# IO.net
KiCad netlist of a schematic drawn in Altium Designer
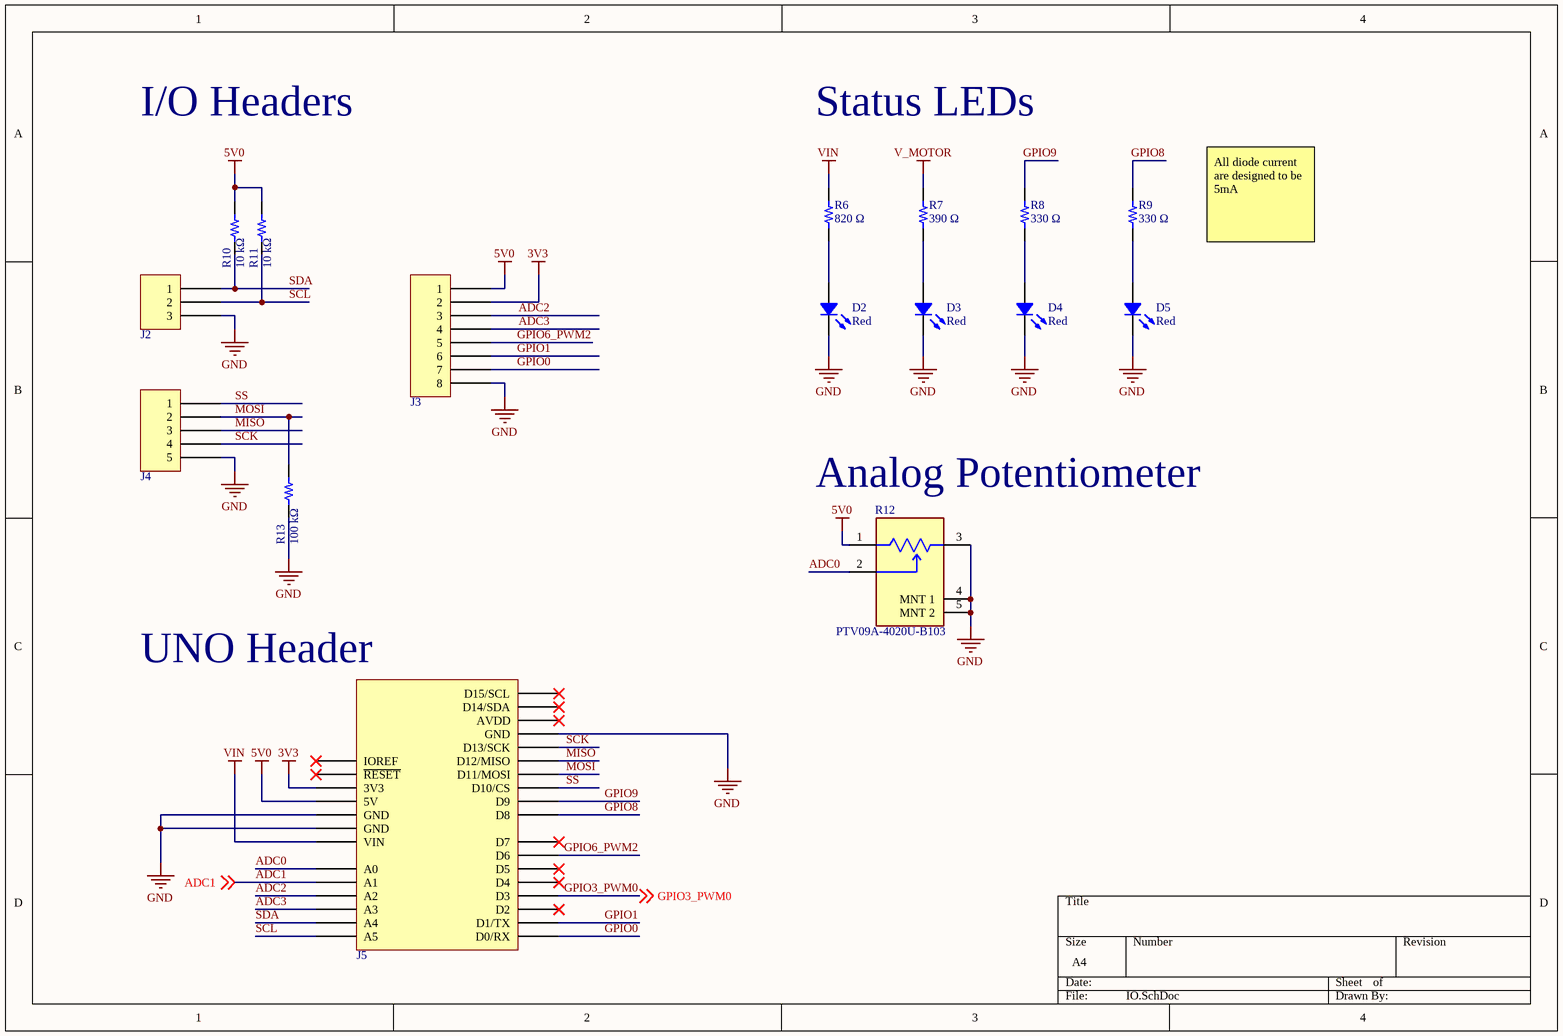
[diagram p0: IO.SchDoc]

(export (version "E")
  (design (tool "Eeschema 10.0.6"))
  (components
    (comp (ref "D2")
      (value "Red")
      (footprint "LED 0603_1608 RED")
      (description "LED RED DIFFUSED 0603 SMD")
      (fields (field (name "PART NUMBER") "150060SS55040") (field (name "MANUFACTURER") "Würth Elektronik"))
      (libsource (lib "Generic Altium Database") (part "LED"))
    )
    (comp (ref "D3")
      (value "Red")
      (footprint "LED 0603_1608 RED")
      (description "LED RED DIFFUSED 0603 SMD")
      (fields (field (name "PART NUMBER") "150060SS55040") (field (name "MANUFACTURER") "Würth Elektronik"))
      (libsource (lib "Generic Altium Database") (part "LED"))
    )
    (comp (ref "D4")
      (value "Red")
      (footprint "LED 0603_1608 RED")
      (description "LED RED DIFFUSED 0603 SMD")
      (fields (field (name "PART NUMBER") "150060SS55040") (field (name "MANUFACTURER") "Würth Elektronik"))
      (libsource (lib "Generic Altium Database") (part "LED"))
    )
    (comp (ref "D5")
      (value "Red")
      (footprint "LED 0603_1608 RED")
      (description "LED RED DIFFUSED 0603 SMD")
      (fields (field (name "PART NUMBER") "150060SS55040") (field (name "MANUFACTURER") "Würth Elektronik"))
      (libsource (lib "Generic Altium Database") (part "LED"))
    )
    (comp (ref "J2")
      (value "0022272031")
      (footprint "MOLEX KK 0022272031")
      (description "CONN HEADER VERT 3POS 2.54MM")
      (fields (field (name "MANUFACTURER") "Molex"))
      (libsource (lib "Generic Altium Database") (part "3 Pin"))
    )
    (comp (ref "J3")
      (value "0022272081")
      (footprint "MOLEX KK 0022272081")
      (description "CONN HEADER VERT 8POS 2.54MM")
      (fields (field (name "MANUFACTURER") "Molex"))
      (libsource (lib "Generic Altium Database") (part "8 Pin"))
    )
    (comp (ref "J4")
      (value "0022272051")
      (footprint "MOLEX KK 0022272051")
      (description "CONN HEADER VERT 5POS 2.54MM")
      (fields (field (name "MANUFACTURER") "Molex"))
      (libsource (lib "Generic Altium Database") (part "5 Pin"))
    )
    (comp (ref "J5")
      (value "920-0088-01")
      (footprint "SCHMARTBOARD - 920-0088-01")
      (description "CONN HDR 8/10P 0.1 GOLD PCB 6PC")
      (fields (field (name "MANUFACTURER") "Schmartboard, Inc."))
      (libsource (lib "Generic Altium Database") (part "Arduino Headers"))
    )
    (comp (ref "R6")
      (value "820 Ω")
      (footprint "RES 0603_1608")
      (description "RES SMD 820 OHM 1% 1/10W 0603")
      (fields (field (name "PART NUMBER") "AC0603FR-07820RL") (field (name "MANUFACTURER") "Yageo"))
      (libsource (lib "Generic Altium Database") (part "Resistor"))
    )
    (comp (ref "R7")
      (value "390 Ω")
      (footprint "RES 0603_1608")
      (description "RES SMD 390 OHM 5% 1/10W 0603")
      (fields (field (name "PART NUMBER") "AC0603JR-07390RL") (field (name "MANUFACTURER") "Yageo"))
      (libsource (lib "Generic Altium Database") (part "Resistor"))
    )
    (comp (ref "R8")
      (value "330 Ω")
      (footprint "RES 0603_1608")
      (description "RES SMD 330 OHM 1% 1/10W 0603")
      (fields (field (name "PART NUMBER") "AC0603FR-07330RL") (field (name "MANUFACTURER") "Yageo"))
      (libsource (lib "Generic Altium Database") (part "Resistor"))
    )
    (comp (ref "R9")
      (value "330 Ω")
      (footprint "RES 0603_1608")
      (description "RES SMD 330 OHM 1% 1/10W 0603")
      (fields (field (name "PART NUMBER") "AC0603FR-07330RL") (field (name "MANUFACTURER") "Yageo"))
      (libsource (lib "Generic Altium Database") (part "Resistor"))
    )
    (comp (ref "R10")
      (value "10 kΩ")
      (footprint "RES 0603_1608")
      (description "RES SMD 10K OHM 1% 1/10W 0603")
      (fields (field (name "PART NUMBER") "AC0603FR-0710KL") (field (name "MANUFACTURER") "Yageo"))
      (libsource (lib "Generic Altium Database") (part "Resistor"))
    )
    (comp (ref "R11")
      (value "10 kΩ")
      (footprint "RES 0603_1608")
      (description "RES SMD 10K OHM 1% 1/10W 0603")
      (fields (field (name "PART NUMBER") "AC0603FR-0710KL") (field (name "MANUFACTURER") "Yageo"))
      (libsource (lib "Generic Altium Database") (part "Resistor"))
    )
    (comp (ref "R12")
      (value "PTV09A-4020U-B103")
      (footprint "FP-PTV09A-4-MFG")
      (description "POT 10K OHM 1/20W CARBON LINEAR")
      (fields (field (name "TOLERANCE") "20%") (field (name "MANUFACTURER") "Bourns Inc."))
      (libsource (lib "Altium Content Vault") (part "3454c451b146ec4d4239c7813666f62"))
    )
    (comp (ref "R13")
      (value "100 kΩ")
      (footprint "RES 0603_1608")
      (description "RES SMD 100K OHM 1% 1/10W 0603")
      (fields (field (name "PART NUMBER") "AC0603FR-07100KL") (field (name "MANUFACTURER") "Yageo"))
      (libsource (lib "Generic Altium Database") (part "Resistor"))
    )
  )
  (nets
    (net (code "1") (name "/ADC0") (class "Default")
      (node (ref "J5") (pin "9") (pinfunction "A0_9") (pintype "passive"))
      (node (ref "R12") (pin "2") (pinfunction "2_2") (pintype "passive"))
    )
    (net (code "2") (name "/ADC2") (class "Default")
      (node (ref "J3") (pin "3") (pinfunction "3_3") (pintype "passive"))
      (node (ref "J5") (pin "11") (pinfunction "A2_11") (pintype "passive"))
    )
    (net (code "3") (name "/ADC3") (class "Default")
      (node (ref "J3") (pin "4") (pinfunction "4_4") (pintype "passive"))
      (node (ref "J5") (pin "12") (pinfunction "A3_12") (pintype "passive"))
    )
    (net (code "4") (name "/GPIO0") (class "Default")
      (node (ref "J3") (pin "7") (pinfunction "7_7") (pintype "passive"))
      (node (ref "J5") (pin "15") (pinfunction "D0/RX_15") (pintype "passive"))
    )
    (net (code "5") (name "/GPIO1") (class "Default")
      (node (ref "J3") (pin "6") (pinfunction "6_6") (pintype "passive"))
      (node (ref "J5") (pin "16") (pinfunction "D1/TX_16") (pintype "passive"))
    )
    (net (code "6") (name "/GPIO6_PWM2") (class "Default")
      (node (ref "J3") (pin "5") (pinfunction "5_5") (pintype "passive"))
      (node (ref "J5") (pin "21") (pinfunction "D6_21") (pintype "passive"))
    )
    (net (code "7") (name "/GPIO8") (class "Default")
      (node (ref "J5") (pin "23") (pinfunction "D8_23") (pintype "passive"))
      (node (ref "R9") (pin "1") (pinfunction "1_1") (pintype "passive"))
    )
    (net (code "8") (name "/GPIO9") (class "Default")
      (node (ref "J5") (pin "24") (pinfunction "D9_24") (pintype "passive"))
      (node (ref "R8") (pin "1") (pinfunction "1_1") (pintype "passive"))
    )
    (net (code "9") (name "/MISO") (class "Default")
      (node (ref "J4") (pin "3") (pinfunction "3_3") (pintype "passive"))
      (node (ref "J5") (pin "27") (pinfunction "D12/MISO_27") (pintype "passive"))
    )
    (net (code "10") (name "/MOSI") (class "Default")
      (node (ref "J4") (pin "2") (pinfunction "2_2") (pintype "passive"))
      (node (ref "J5") (pin "26") (pinfunction "D11/MOSI_26") (pintype "passive"))
      (node (ref "R13") (pin "1") (pinfunction "1_1") (pintype "passive"))
    )
    (net (code "11") (name "/SCK") (class "Default")
      (node (ref "J4") (pin "4") (pinfunction "4_4") (pintype "passive"))
      (node (ref "J5") (pin "28") (pinfunction "D13/SCK_28") (pintype "passive"))
    )
    (net (code "12") (name "/SCL") (class "Default")
      (node (ref "J2") (pin "2") (pinfunction "2_2") (pintype "passive"))
      (node (ref "J5") (pin "14") (pinfunction "A5_14") (pintype "passive"))
      (node (ref "R11") (pin "2") (pinfunction "2_2") (pintype "passive"))
    )
    (net (code "13") (name "/SDA") (class "Default")
      (node (ref "J2") (pin "1") (pinfunction "1_1") (pintype "passive"))
      (node (ref "J5") (pin "13") (pinfunction "A4_13") (pintype "passive"))
      (node (ref "R10") (pin "2") (pinfunction "2_2") (pintype "passive"))
    )
    (net (code "14") (name "/SS") (class "Default")
      (node (ref "J4") (pin "1") (pinfunction "1_1") (pintype "passive"))
      (node (ref "J5") (pin "25") (pinfunction "D10/CS_25") (pintype "passive"))
    )
    (net (code "15") (name "3V3") (class "Default")
      (node (ref "J3") (pin "2") (pinfunction "2_2") (pintype "passive"))
      (node (ref "J5") (pin "4") (pinfunction "3V3_4") (pintype "passive"))
    )
    (net (code "16") (name "5V0") (class "Default")
      (node (ref "J3") (pin "1") (pinfunction "1_1") (pintype "passive"))
      (node (ref "J5") (pin "5") (pinfunction "5V_5") (pintype "passive"))
      (node (ref "R10") (pin "1") (pinfunction "1_1") (pintype "passive"))
      (node (ref "R11") (pin "1") (pinfunction "1_1") (pintype "passive"))
      (node (ref "R12") (pin "1") (pinfunction "1_1") (pintype "passive"))
    )
    (net (code "17") (name "ADC1") (class "Default")
      (node (ref "J5") (pin "10") (pinfunction "A1_10") (pintype "passive"))
    )
    (net (code "18") (name "GND") (class "Default")
      (node (ref "D2") (pin "2") (pinfunction "2_2") (pintype "passive"))
      (node (ref "D3") (pin "2") (pinfunction "2_2") (pintype "passive"))
      (node (ref "D4") (pin "2") (pinfunction "2_2") (pintype "passive"))
      (node (ref "D5") (pin "2") (pinfunction "2_2") (pintype "passive"))
      (node (ref "J2") (pin "3") (pinfunction "3_3") (pintype "passive"))
      (node (ref "J3") (pin "8") (pinfunction "8_8") (pintype "passive"))
      (node (ref "J4") (pin "5") (pinfunction "5_5") (pintype "passive"))
      (node (ref "J5") (pin "29") (pinfunction "GND_29") (pintype "passive"))
      (node (ref "J5") (pin "6") (pinfunction "GND_6") (pintype "passive"))
      (node (ref "J5") (pin "7") (pinfunction "GND_7") (pintype "passive"))
      (node (ref "R12") (pin "3") (pinfunction "3_3") (pintype "passive"))
      (node (ref "R12") (pin "4") (pinfunction "MNT_1_4") (pintype "passive"))
      (node (ref "R12") (pin "5") (pinfunction "MNT_2_5") (pintype "passive"))
      (node (ref "R13") (pin "2") (pinfunction "2_2") (pintype "passive"))
    )
    (net (code "19") (name "GPIO3_PWM0") (class "Default")
      (node (ref "J5") (pin "18") (pinfunction "D3_18") (pintype "passive"))
    )
    (net (code "20") (name "Net-(D2-Pad1)") (class "Default")
      (node (ref "D2") (pin "1") (pinfunction "1_1") (pintype "passive"))
      (node (ref "R6") (pin "2") (pinfunction "2_2") (pintype "passive"))
    )
    (net (code "21") (name "Net-(D3-Pad1)") (class "Default")
      (node (ref "D3") (pin "1") (pinfunction "1_1") (pintype "passive"))
      (node (ref "R7") (pin "2") (pinfunction "2_2") (pintype "passive"))
    )
    (net (code "22") (name "Net-(D4-Pad1)") (class "Default")
      (node (ref "D4") (pin "1") (pinfunction "1_1") (pintype "passive"))
      (node (ref "R8") (pin "2") (pinfunction "2_2") (pintype "passive"))
    )
    (net (code "23") (name "Net-(D5-Pad1)") (class "Default")
      (node (ref "D5") (pin "1") (pinfunction "1_1") (pintype "passive"))
      (node (ref "R9") (pin "2") (pinfunction "2_2") (pintype "passive"))
    )
    (net (code "24") (name "VIN") (class "Default")
      (node (ref "J5") (pin "8") (pinfunction "VIN_8") (pintype "passive"))
      (node (ref "R6") (pin "1") (pinfunction "1_1") (pintype "passive"))
    )
    (net (code "25") (name "V_MOTOR") (class "Default")
      (node (ref "R7") (pin "1") (pinfunction "1_1") (pintype "passive"))
    )
    (net (code "26") (name "unconnected-(J5-AVDD-Pad30)") (class "Default")
      (node (ref "J5") (pin "30") (pinfunction "AVDD_30") (pintype "passive+no_connect"))
    )
    (net (code "27") (name "unconnected-(J5-D2-Pad17)") (class "Default")
      (node (ref "J5") (pin "17") (pinfunction "D2_17") (pintype "passive+no_connect"))
    )
    (net (code "28") (name "unconnected-(J5-D4-Pad19)") (class "Default")
      (node (ref "J5") (pin "19") (pinfunction "D4_19") (pintype "passive+no_connect"))
    )
    (net (code "29") (name "unconnected-(J5-D5-Pad20)") (class "Default")
      (node (ref "J5") (pin "20") (pinfunction "D5_20") (pintype "passive+no_connect"))
    )
    (net (code "30") (name "unconnected-(J5-D7-Pad22)") (class "Default")
      (node (ref "J5") (pin "22") (pinfunction "D7_22") (pintype "passive+no_connect"))
    )
    (net (code "31") (name "unconnected-(J5-D14{slash}SDA-Pad31)") (class "Default")
      (node (ref "J5") (pin "31") (pinfunction "D14/SDA_31") (pintype "passive+no_connect"))
    )
    (net (code "32") (name "unconnected-(J5-D15{slash}SCL-Pad32)") (class "Default")
      (node (ref "J5") (pin "32") (pinfunction "D15/SCL_32") (pintype "passive+no_connect"))
    )
    (net (code "33") (name "unconnected-(J5-IOREF-Pad2)") (class "Default")
      (node (ref "J5") (pin "2") (pinfunction "IOREF_2") (pintype "passive+no_connect"))
    )
    (net (code "34") (name "unconnected-(J5-~{RESET}-Pad3)") (class "Default")
      (node (ref "J5") (pin "3") (pinfunction "~{RESET}_3") (pintype "passive+no_connect"))
    )
  )
)
